# DAQ_Terminal.net
KiCad netlist of a schematic drawn in EAGLE
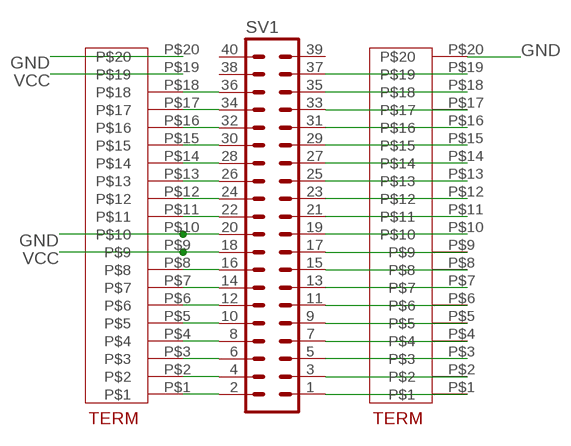
[diagram p0: schematic, sheet 1]

(export (version "E")
  (design (tool "Eeschema 10.0.6"))
  (components
    (comp (ref "SV1")
      (value "MA20-2")
      (footprint "eagle-import:MA20-2")
      (libsource (lib "eagle-import") (part "MA20-2"))
    )
    (comp (ref "U$1")
      (value "20TERM")
      (footprint "eagle-import:20TERM")
      (libsource (lib "eagle-import") (part "20TERM"))
    )
    (comp (ref "U$2")
      (value "20TERM")
      (footprint "eagle-import:20TERM")
      (libsource (lib "eagle-import") (part "20TERM"))
    )
  )
  (nets
    (net (code "1") (name "/GND") (class "Default")
      (node (ref "SV1") (pin "20") (pinfunction "20_20") (pintype "passive"))
      (node (ref "U$1") (pin "P$20") (pinfunction "P$20_P$20") (pintype "bidirectional"))
      (node (ref "U$2") (pin "P$10") (pinfunction "P$10_P$10") (pintype "bidirectional"))
      (node (ref "U$2") (pin "P$20") (pinfunction "P$20_P$20") (pintype "bidirectional"))
    )
    (net (code "2") (name "/VCC") (class "Default")
      (node (ref "SV1") (pin "18") (pinfunction "18_18") (pintype "passive"))
      (node (ref "U$2") (pin "P$19") (pinfunction "P$19_P$19") (pintype "bidirectional"))
      (node (ref "U$2") (pin "P$9") (pinfunction "P$9_P$9") (pintype "bidirectional"))
    )
    (net (code "3") (name "Net-(SV1-Pad1)") (class "Default")
      (node (ref "SV1") (pin "1") (pinfunction "1_1") (pintype "passive"))
      (node (ref "U$1") (pin "P$1") (pinfunction "P$1_P$1") (pintype "bidirectional"))
    )
    (net (code "4") (name "Net-(SV1-Pad2)") (class "Default")
      (node (ref "SV1") (pin "2") (pinfunction "2_2") (pintype "passive"))
      (node (ref "U$2") (pin "P$1") (pinfunction "P$1_P$1") (pintype "bidirectional"))
    )
    (net (code "5") (name "Net-(SV1-Pad3)") (class "Default")
      (node (ref "SV1") (pin "3") (pinfunction "3_3") (pintype "passive"))
      (node (ref "U$1") (pin "P$2") (pinfunction "P$2_P$2") (pintype "bidirectional"))
    )
    (net (code "6") (name "Net-(SV1-Pad4)") (class "Default")
      (node (ref "SV1") (pin "4") (pinfunction "4_4") (pintype "passive"))
      (node (ref "U$2") (pin "P$2") (pinfunction "P$2_P$2") (pintype "bidirectional"))
    )
    (net (code "7") (name "Net-(SV1-Pad5)") (class "Default")
      (node (ref "SV1") (pin "5") (pinfunction "5_5") (pintype "passive"))
      (node (ref "U$1") (pin "P$3") (pinfunction "P$3_P$3") (pintype "bidirectional"))
    )
    (net (code "8") (name "Net-(SV1-Pad6)") (class "Default")
      (node (ref "SV1") (pin "6") (pinfunction "6_6") (pintype "passive"))
      (node (ref "U$2") (pin "P$3") (pinfunction "P$3_P$3") (pintype "bidirectional"))
    )
    (net (code "9") (name "Net-(SV1-Pad7)") (class "Default")
      (node (ref "SV1") (pin "7") (pinfunction "7_7") (pintype "passive"))
      (node (ref "U$1") (pin "P$4") (pinfunction "P$4_P$4") (pintype "bidirectional"))
    )
    (net (code "10") (name "Net-(SV1-Pad8)") (class "Default")
      (node (ref "SV1") (pin "8") (pinfunction "8_8") (pintype "passive"))
      (node (ref "U$2") (pin "P$4") (pinfunction "P$4_P$4") (pintype "bidirectional"))
    )
    (net (code "11") (name "Net-(SV1-Pad9)") (class "Default")
      (node (ref "SV1") (pin "9") (pinfunction "9_9") (pintype "passive"))
      (node (ref "U$1") (pin "P$5") (pinfunction "P$5_P$5") (pintype "bidirectional"))
    )
    (net (code "12") (name "Net-(SV1-Pad10)") (class "Default")
      (node (ref "SV1") (pin "10") (pinfunction "10_10") (pintype "passive"))
      (node (ref "U$2") (pin "P$5") (pinfunction "P$5_P$5") (pintype "bidirectional"))
    )
    (net (code "13") (name "Net-(SV1-Pad11)") (class "Default")
      (node (ref "SV1") (pin "11") (pinfunction "11_11") (pintype "passive"))
      (node (ref "U$1") (pin "P$6") (pinfunction "P$6_P$6") (pintype "bidirectional"))
    )
    (net (code "14") (name "Net-(SV1-Pad12)") (class "Default")
      (node (ref "SV1") (pin "12") (pinfunction "12_12") (pintype "passive"))
      (node (ref "U$2") (pin "P$6") (pinfunction "P$6_P$6") (pintype "bidirectional"))
    )
    (net (code "15") (name "Net-(SV1-Pad13)") (class "Default")
      (node (ref "SV1") (pin "13") (pinfunction "13_13") (pintype "passive"))
      (node (ref "U$1") (pin "P$7") (pinfunction "P$7_P$7") (pintype "bidirectional"))
    )
    (net (code "16") (name "Net-(SV1-Pad14)") (class "Default")
      (node (ref "SV1") (pin "14") (pinfunction "14_14") (pintype "passive"))
      (node (ref "U$2") (pin "P$7") (pinfunction "P$7_P$7") (pintype "bidirectional"))
    )
    (net (code "17") (name "Net-(SV1-Pad15)") (class "Default")
      (node (ref "SV1") (pin "15") (pinfunction "15_15") (pintype "passive"))
      (node (ref "U$1") (pin "P$8") (pinfunction "P$8_P$8") (pintype "bidirectional"))
    )
    (net (code "18") (name "Net-(SV1-Pad16)") (class "Default")
      (node (ref "SV1") (pin "16") (pinfunction "16_16") (pintype "passive"))
      (node (ref "U$2") (pin "P$8") (pinfunction "P$8_P$8") (pintype "bidirectional"))
    )
    (net (code "19") (name "Net-(SV1-Pad17)") (class "Default")
      (node (ref "SV1") (pin "17") (pinfunction "17_17") (pintype "passive"))
      (node (ref "U$1") (pin "P$9") (pinfunction "P$9_P$9") (pintype "bidirectional"))
    )
    (net (code "20") (name "Net-(SV1-Pad19)") (class "Default")
      (node (ref "SV1") (pin "19") (pinfunction "19_19") (pintype "passive"))
      (node (ref "U$1") (pin "P$10") (pinfunction "P$10_P$10") (pintype "bidirectional"))
    )
    (net (code "21") (name "Net-(SV1-Pad21)") (class "Default")
      (node (ref "SV1") (pin "21") (pinfunction "21_21") (pintype "passive"))
      (node (ref "U$1") (pin "P$11") (pinfunction "P$11_P$11") (pintype "bidirectional"))
    )
    (net (code "22") (name "Net-(SV1-Pad22)") (class "Default")
      (node (ref "SV1") (pin "22") (pinfunction "22_22") (pintype "passive"))
      (node (ref "U$2") (pin "P$11") (pinfunction "P$11_P$11") (pintype "bidirectional"))
    )
    (net (code "23") (name "Net-(SV1-Pad23)") (class "Default")
      (node (ref "SV1") (pin "23") (pinfunction "23_23") (pintype "passive"))
      (node (ref "U$1") (pin "P$12") (pinfunction "P$12_P$12") (pintype "bidirectional"))
    )
    (net (code "24") (name "Net-(SV1-Pad24)") (class "Default")
      (node (ref "SV1") (pin "24") (pinfunction "24_24") (pintype "passive"))
      (node (ref "U$2") (pin "P$12") (pinfunction "P$12_P$12") (pintype "bidirectional"))
    )
    (net (code "25") (name "Net-(SV1-Pad25)") (class "Default")
      (node (ref "SV1") (pin "25") (pinfunction "25_25") (pintype "passive"))
      (node (ref "U$1") (pin "P$13") (pinfunction "P$13_P$13") (pintype "bidirectional"))
    )
    (net (code "26") (name "Net-(SV1-Pad26)") (class "Default")
      (node (ref "SV1") (pin "26") (pinfunction "26_26") (pintype "passive"))
      (node (ref "U$2") (pin "P$13") (pinfunction "P$13_P$13") (pintype "bidirectional"))
    )
    (net (code "27") (name "Net-(SV1-Pad27)") (class "Default")
      (node (ref "SV1") (pin "27") (pinfunction "27_27") (pintype "passive"))
      (node (ref "U$1") (pin "P$14") (pinfunction "P$14_P$14") (pintype "bidirectional"))
    )
    (net (code "28") (name "Net-(SV1-Pad28)") (class "Default")
      (node (ref "SV1") (pin "28") (pinfunction "28_28") (pintype "passive"))
      (node (ref "U$2") (pin "P$14") (pinfunction "P$14_P$14") (pintype "bidirectional"))
    )
    (net (code "29") (name "Net-(SV1-Pad29)") (class "Default")
      (node (ref "SV1") (pin "29") (pinfunction "29_29") (pintype "passive"))
      (node (ref "U$1") (pin "P$15") (pinfunction "P$15_P$15") (pintype "bidirectional"))
    )
    (net (code "30") (name "Net-(SV1-Pad30)") (class "Default")
      (node (ref "SV1") (pin "30") (pinfunction "30_30") (pintype "passive"))
      (node (ref "U$2") (pin "P$15") (pinfunction "P$15_P$15") (pintype "bidirectional"))
    )
    (net (code "31") (name "Net-(SV1-Pad31)") (class "Default")
      (node (ref "SV1") (pin "31") (pinfunction "31_31") (pintype "passive"))
      (node (ref "U$1") (pin "P$16") (pinfunction "P$16_P$16") (pintype "bidirectional"))
    )
    (net (code "32") (name "Net-(SV1-Pad32)") (class "Default")
      (node (ref "SV1") (pin "32") (pinfunction "32_32") (pintype "passive"))
      (node (ref "U$2") (pin "P$16") (pinfunction "P$16_P$16") (pintype "bidirectional"))
    )
    (net (code "33") (name "Net-(SV1-Pad33)") (class "Default")
      (node (ref "SV1") (pin "33") (pinfunction "33_33") (pintype "passive"))
      (node (ref "U$1") (pin "P$17") (pinfunction "P$17_P$17") (pintype "bidirectional"))
    )
    (net (code "34") (name "Net-(SV1-Pad34)") (class "Default")
      (node (ref "SV1") (pin "34") (pinfunction "34_34") (pintype "passive"))
      (node (ref "U$2") (pin "P$17") (pinfunction "P$17_P$17") (pintype "bidirectional"))
    )
    (net (code "35") (name "Net-(SV1-Pad35)") (class "Default")
      (node (ref "SV1") (pin "35") (pinfunction "35_35") (pintype "passive"))
      (node (ref "U$1") (pin "P$18") (pinfunction "P$18_P$18") (pintype "bidirectional"))
    )
    (net (code "36") (name "Net-(SV1-Pad36)") (class "Default")
      (node (ref "SV1") (pin "36") (pinfunction "36_36") (pintype "passive"))
      (node (ref "U$2") (pin "P$18") (pinfunction "P$18_P$18") (pintype "bidirectional"))
    )
    (net (code "37") (name "Net-(SV1-Pad37)") (class "Default")
      (node (ref "SV1") (pin "37") (pinfunction "37_37") (pintype "passive"))
      (node (ref "U$1") (pin "P$19") (pinfunction "P$19_P$19") (pintype "bidirectional"))
    )
    (net (code "38") (name "unconnected-(SV1-Pad38)") (class "Default")
      (node (ref "SV1") (pin "38") (pinfunction "38_38") (pintype "passive"))
    )
    (net (code "39") (name "unconnected-(SV1-Pad39)") (class "Default")
      (node (ref "SV1") (pin "39") (pinfunction "39_39") (pintype "passive"))
    )
    (net (code "40") (name "unconnected-(SV1-Pad40)") (class "Default")
      (node (ref "SV1") (pin "40") (pinfunction "40_40") (pintype "passive"))
    )
  )
)
